# Ther.net
KiCad netlist of a schematic drawn in Altium Designer
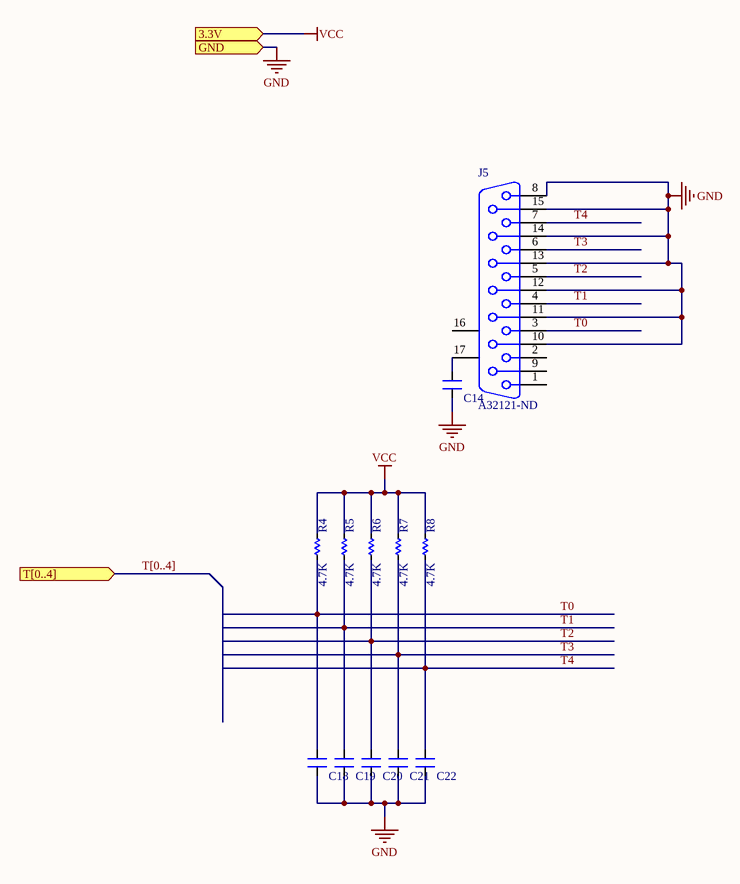
[diagram p0: Ther.SchDoc]

(export (version "E")
  (design (tool "Eeschema 10.0.6"))
  (components
    (comp (ref "C14") (value "10uF") (footprint "CN-SMD-0603_big") (libsource (lib "nhan") (part "CN")))
    (comp (ref "C18") (value "10uF") (footprint "CN-SMD-0603_big") (libsource (lib "nhan") (part "CN")))
    (comp (ref "C19") (value "10uF") (footprint "CN-SMD-0603_big") (libsource (lib "nhan") (part "CN")))
    (comp (ref "C20") (value "10uF") (footprint "CN-SMD-0603_big") (libsource (lib "nhan") (part "CN")))
    (comp (ref "C21") (value "10uF") (footprint "CN-SMD-0603_big") (libsource (lib "nhan") (part "CN")))
    (comp (ref "C22") (value "10uF") (footprint "CN-SMD-0603_big") (libsource (lib "nhan") (part "CN")))
    (comp (ref "J5")
      (value "A32121-ND")
      (footprint "DB15")
      (description "Receptacle Assembly, 15 Position, Right Angle")
      (fields (field (name "PUBLISHER") "Altium Limited"))
      (libsource (lib "nhan") (part "DB15"))
    )
    (comp (ref "R4") (value "4.7K") (footprint "RES-SMD-0603_BIG") (libsource (lib "nhan") (part "R")))
    (comp (ref "R5") (value "4.7K") (footprint "RES-SMD-0603_BIG") (libsource (lib "nhan") (part "R")))
    (comp (ref "R6") (value "4.7K") (footprint "RES-SMD-0603_BIG") (libsource (lib "nhan") (part "R")))
    (comp (ref "R7") (value "4.7K") (footprint "RES-SMD-0603_BIG") (libsource (lib "nhan") (part "R")))
    (comp (ref "R8") (value "4.7K") (footprint "RES-SMD-0603_BIG") (libsource (lib "nhan") (part "R")))
  )
  (nets
    (net (code "1") (name "/T0") (class "Default")
      (node (ref "C18") (pin "2") (pinfunction "2_2") (pintype "passive"))
      (node (ref "J5") (pin "3") (pinfunction "3_3") (pintype "passive"))
      (node (ref "R4") (pin "2") (pinfunction "2_2") (pintype "passive"))
    )
    (net (code "2") (name "/T1") (class "Default")
      (node (ref "C19") (pin "2") (pinfunction "2_2") (pintype "passive"))
      (node (ref "J5") (pin "4") (pinfunction "4_4") (pintype "passive"))
      (node (ref "R5") (pin "2") (pinfunction "2_2") (pintype "passive"))
    )
    (net (code "3") (name "/T2") (class "Default")
      (node (ref "C20") (pin "2") (pinfunction "2_2") (pintype "passive"))
      (node (ref "J5") (pin "5") (pinfunction "5_5") (pintype "passive"))
      (node (ref "R6") (pin "2") (pinfunction "2_2") (pintype "passive"))
    )
    (net (code "4") (name "/T3") (class "Default")
      (node (ref "C21") (pin "2") (pinfunction "2_2") (pintype "passive"))
      (node (ref "J5") (pin "6") (pinfunction "6_6") (pintype "passive"))
      (node (ref "R7") (pin "2") (pinfunction "2_2") (pintype "passive"))
    )
    (net (code "5") (name "/T4") (class "Default")
      (node (ref "C22") (pin "2") (pinfunction "2_2") (pintype "passive"))
      (node (ref "J5") (pin "7") (pinfunction "7_7") (pintype "passive"))
      (node (ref "R8") (pin "2") (pinfunction "2_2") (pintype "passive"))
    )
    (net (code "7") (name "GND") (class "Default")
      (node (ref "C14") (pin "1") (pinfunction "1_1") (pintype "passive"))
      (node (ref "C18") (pin "1") (pinfunction "1_1") (pintype "passive"))
      (node (ref "C19") (pin "1") (pinfunction "1_1") (pintype "passive"))
      (node (ref "C20") (pin "1") (pinfunction "1_1") (pintype "passive"))
      (node (ref "C21") (pin "1") (pinfunction "1_1") (pintype "passive"))
      (node (ref "C22") (pin "1") (pinfunction "1_1") (pintype "passive"))
      (node (ref "J5") (pin "10") (pinfunction "10_10") (pintype "passive"))
      (node (ref "J5") (pin "11") (pinfunction "11_11") (pintype "passive"))
      (node (ref "J5") (pin "12") (pinfunction "12_12") (pintype "passive"))
      (node (ref "J5") (pin "13") (pinfunction "13_13") (pintype "passive"))
      (node (ref "J5") (pin "14") (pinfunction "14_14") (pintype "passive"))
      (node (ref "J5") (pin "15") (pinfunction "15_15") (pintype "passive"))
      (node (ref "J5") (pin "8") (pinfunction "8_8") (pintype "passive"))
    )
    (net (code "8") (name "Net-(J5-MH2)") (class "Default")
      (node (ref "C14") (pin "2") (pinfunction "2_2") (pintype "passive"))
      (node (ref "J5") (pin "17") (pinfunction "MH2_17") (pintype "passive"))
    )
    (net (code "9") (name "VCC") (class "Default")
      (node (ref "R4") (pin "1") (pinfunction "1_1") (pintype "passive"))
      (node (ref "R5") (pin "1") (pinfunction "1_1") (pintype "passive"))
      (node (ref "R6") (pin "1") (pinfunction "1_1") (pintype "passive"))
      (node (ref "R7") (pin "1") (pinfunction "1_1") (pintype "passive"))
      (node (ref "R8") (pin "1") (pinfunction "1_1") (pintype "passive"))
    )
    (net (code "10") (name "unconnected-(J5-MH1-Pad16)") (class "Default")
      (node (ref "J5") (pin "16") (pinfunction "MH1_16") (pintype "passive"))
    )
    (net (code "11") (name "unconnected-(J5-Pad1)") (class "Default")
      (node (ref "J5") (pin "1") (pinfunction "1_1") (pintype "passive"))
    )
    (net (code "12") (name "unconnected-(J5-Pad2)") (class "Default")
      (node (ref "J5") (pin "2") (pinfunction "2_2") (pintype "passive"))
    )
    (net (code "13") (name "unconnected-(J5-Pad9)") (class "Default")
      (node (ref "J5") (pin "9") (pinfunction "9_9") (pintype "passive"))
    )
  )
)
